# M044X.net
KiCad netlist of a schematic drawn in EAGLE
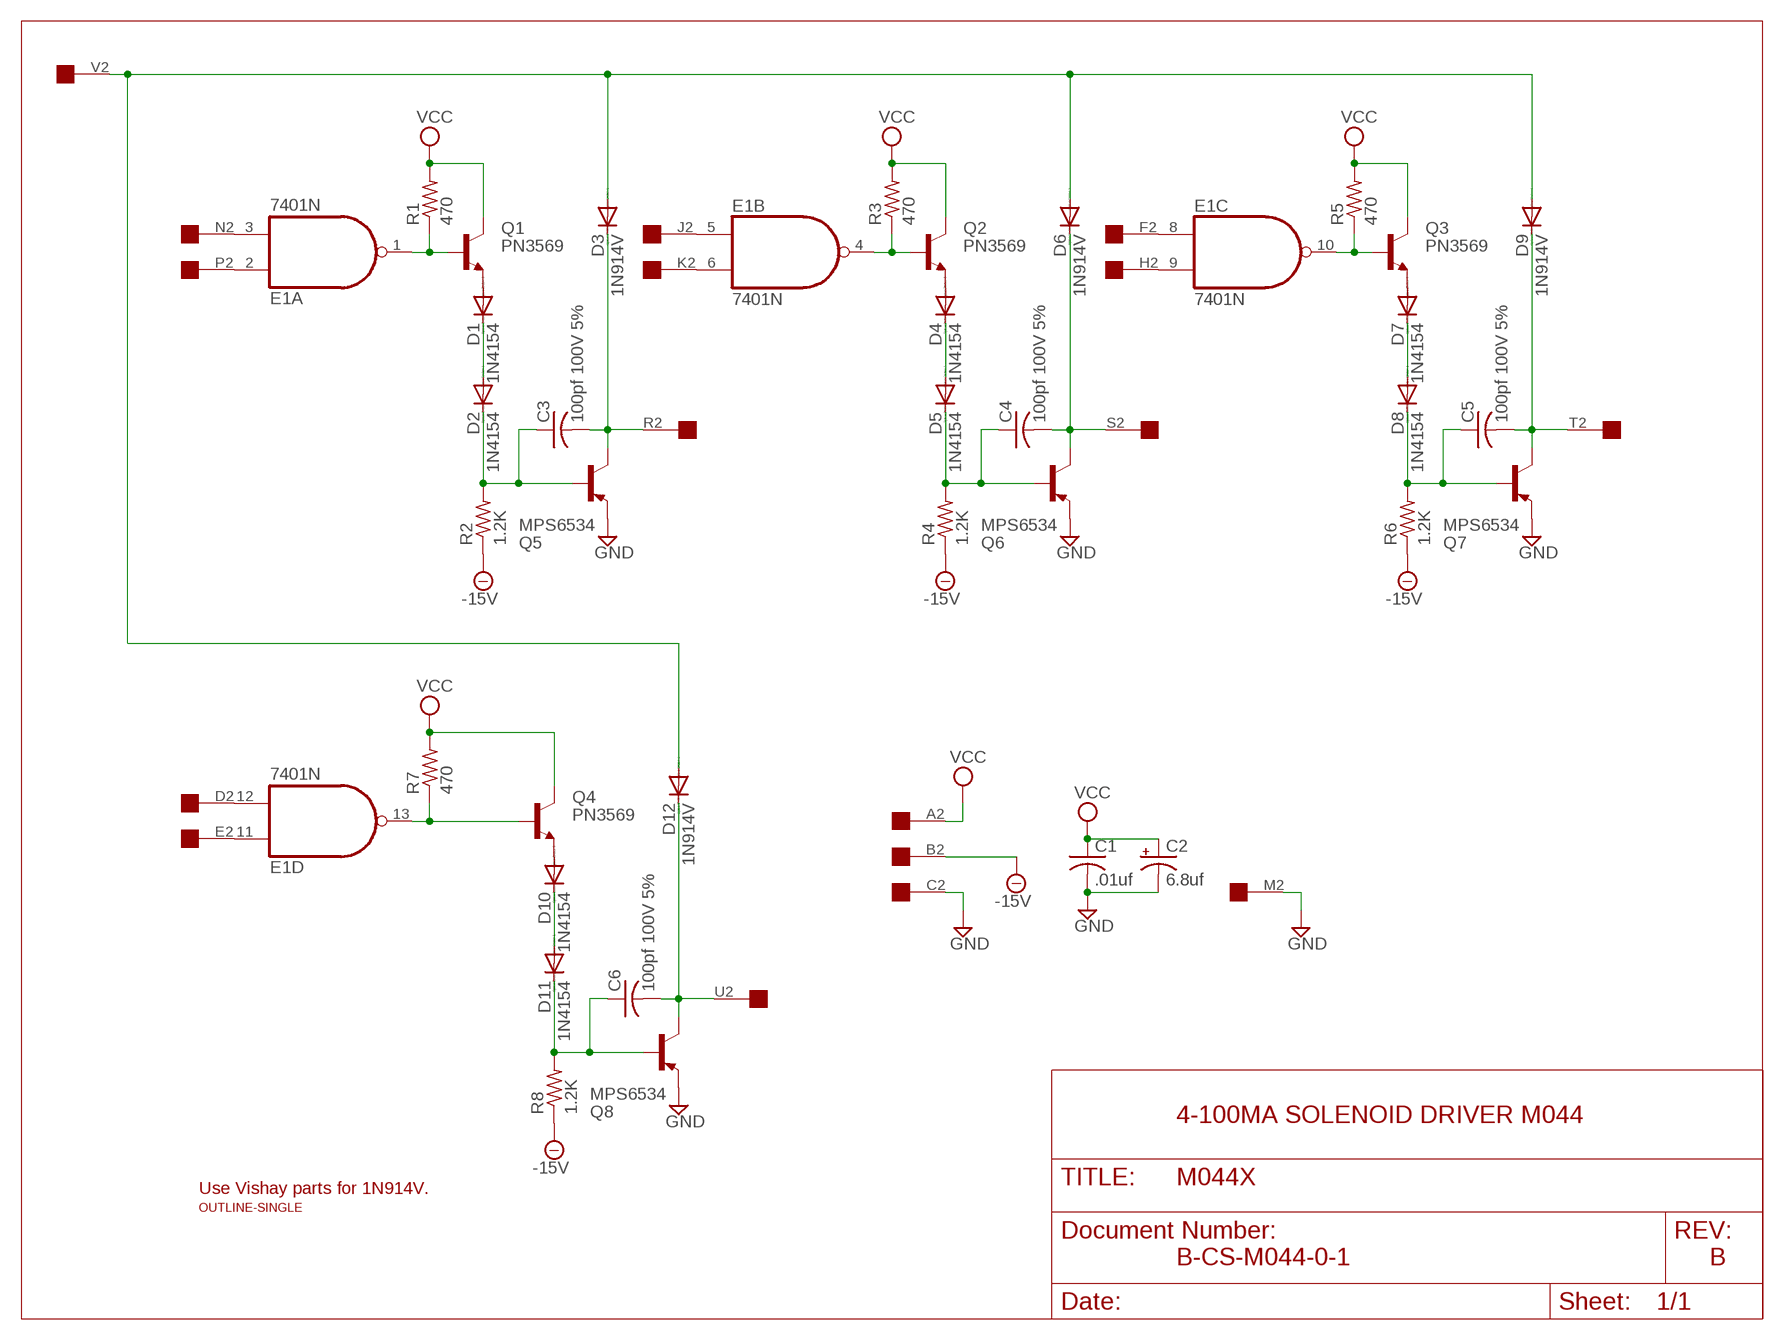
[diagram p0: schematic, sheet 1]

(export (version "E")
  (design (tool "Eeschema 10.0.6"))
  (components
    (comp (ref "C1")
      (value ".01uf")
      (footprint "eagle-import:C050-025X075")
      (libsource (lib "eagle-import") (part "C-US050-025X075"))
    )
    (comp (ref "C2")
      (value "6.8uf")
      (footprint "eagle-import:E15-5")
      (libsource (lib "eagle-import") (part "CPOL-USE15-5AXIAL"))
    )
    (comp (ref "C3")
      (value "100pf 100V 5%")
      (footprint "eagle-import:C050-025X075")
      (libsource (lib "eagle-import") (part "C-US050-025X075"))
    )
    (comp (ref "C4")
      (value "100pf 100V 5%")
      (footprint "eagle-import:C050-025X075")
      (libsource (lib "eagle-import") (part "C-US050-025X075"))
    )
    (comp (ref "C5")
      (value "100pf 100V 5%")
      (footprint "eagle-import:C050-025X075")
      (libsource (lib "eagle-import") (part "C-US050-025X075"))
    )
    (comp (ref "C6")
      (value "100pf 100V 5%")
      (footprint "eagle-import:C050-025X075")
      (libsource (lib "eagle-import") (part "C-US050-025X075"))
    )
    (comp (ref "D1")
      (value "1N4154")
      (footprint "eagle-import:DO35-10")
      (libsource (lib "eagle-import") (part "1N4148DO35-10"))
    )
    (comp (ref "D2")
      (value "1N4154")
      (footprint "eagle-import:DO35-10")
      (libsource (lib "eagle-import") (part "1N4148DO35-10"))
    )
    (comp (ref "D3")
      (value "1N914V")
      (footprint "eagle-import:DO35-10")
      (libsource (lib "eagle-import") (part "1N4148DO35-10"))
    )
    (comp (ref "D4")
      (value "1N4154")
      (footprint "eagle-import:DO35-10")
      (libsource (lib "eagle-import") (part "1N4148DO35-10"))
    )
    (comp (ref "D5")
      (value "1N4154")
      (footprint "eagle-import:DO35-10")
      (libsource (lib "eagle-import") (part "1N4148DO35-10"))
    )
    (comp (ref "D6")
      (value "1N914V")
      (footprint "eagle-import:DO35-10")
      (libsource (lib "eagle-import") (part "1N4148DO35-10"))
    )
    (comp (ref "D7")
      (value "1N4154")
      (footprint "eagle-import:DO35-10")
      (libsource (lib "eagle-import") (part "1N4148DO35-10"))
    )
    (comp (ref "D8")
      (value "1N4154")
      (footprint "eagle-import:DO35-10")
      (libsource (lib "eagle-import") (part "1N4148DO35-10"))
    )
    (comp (ref "D9")
      (value "1N914V")
      (footprint "eagle-import:DO35-10")
      (libsource (lib "eagle-import") (part "1N4148DO35-10"))
    )
    (comp (ref "D10")
      (value "1N4154")
      (footprint "eagle-import:DO35-10")
      (libsource (lib "eagle-import") (part "1N4148DO35-10"))
    )
    (comp (ref "D11")
      (value "1N4154")
      (footprint "eagle-import:DO35-10")
      (libsource (lib "eagle-import") (part "1N4148DO35-10"))
    )
    (comp (ref "D12")
      (value "1N914V")
      (footprint "eagle-import:DO35-10")
      (libsource (lib "eagle-import") (part "1N4148DO35-10"))
    )
    (comp (ref "E1")
      (value "7401N")
      (footprint "eagle-import:DIL14")
      (libsource (lib "eagle-import") (part "7401NLS"))
    )
    (comp (ref "Q1")
      (value "PN3569")
      (footprint "eagle-import:TO39")
      (libsource (lib "eagle-import") (part "2N3019"))
    )
    (comp (ref "Q2")
      (value "PN3569")
      (footprint "eagle-import:TO39")
      (libsource (lib "eagle-import") (part "2N3019"))
    )
    (comp (ref "Q3")
      (value "PN3569")
      (footprint "eagle-import:TO39")
      (libsource (lib "eagle-import") (part "2N3019"))
    )
    (comp (ref "Q4")
      (value "PN3569")
      (footprint "eagle-import:TO39")
      (libsource (lib "eagle-import") (part "2N3019"))
    )
    (comp (ref "Q5")
      (value "MPS6534")
      (footprint "eagle-import:TO39")
      (libsource (lib "eagle-import") (part "-PNP-TO39-EBC2N2904"))
    )
    (comp (ref "Q6")
      (value "MPS6534")
      (footprint "eagle-import:TO39")
      (libsource (lib "eagle-import") (part "-PNP-TO39-EBC2N2904"))
    )
    (comp (ref "Q7")
      (value "MPS6534")
      (footprint "eagle-import:TO39")
      (libsource (lib "eagle-import") (part "-PNP-TO39-EBC2N2904"))
    )
    (comp (ref "Q8")
      (value "MPS6534")
      (footprint "eagle-import:TO39")
      (libsource (lib "eagle-import") (part "-PNP-TO39-EBC2N2904"))
    )
    (comp (ref "R1")
      (value "470")
      (footprint "eagle-import:0207_10")
      (libsource (lib "eagle-import") (part "R-US_0207/10"))
    )
    (comp (ref "R2")
      (value "1.2K")
      (footprint "eagle-import:0207_10")
      (libsource (lib "eagle-import") (part "R-US_0207/10"))
    )
    (comp (ref "R3")
      (value "470")
      (footprint "eagle-import:0207_10")
      (libsource (lib "eagle-import") (part "R-US_0207/10"))
    )
    (comp (ref "R4")
      (value "1.2K")
      (footprint "eagle-import:0207_10")
      (libsource (lib "eagle-import") (part "R-US_0207/10"))
    )
    (comp (ref "R5")
      (value "470")
      (footprint "eagle-import:0207_10")
      (libsource (lib "eagle-import") (part "R-US_0207/10"))
    )
    (comp (ref "R6")
      (value "1.2K")
      (footprint "eagle-import:0207_10")
      (libsource (lib "eagle-import") (part "R-US_0207/10"))
    )
    (comp (ref "R7")
      (value "470")
      (footprint "eagle-import:0207_10")
      (libsource (lib "eagle-import") (part "R-US_0207/10"))
    )
    (comp (ref "R8")
      (value "1.2K")
      (footprint "eagle-import:0207_10")
      (libsource (lib "eagle-import") (part "R-US_0207/10"))
    )
    (comp (ref "U$1")
      (value "OUTLINE-SINGLE")
      (footprint "eagle-import:SINGLE")
      (libsource (lib "eagle-import") (part "OUTLINE-SINGLE"))
    )
    (comp (ref "U$2")
      (value "EDGE-1")
      (footprint "eagle-import:EDGE-CON1")
      (libsource (lib "eagle-import") (part "EDGE-1"))
    )
  )
  (nets
    (net (code "1") (name "-15V") (class "Default")
      (node (ref "R2") (pin "1") (pinfunction "1_1") (pintype "passive"))
      (node (ref "R4") (pin "1") (pinfunction "1_1") (pintype "passive"))
      (node (ref "R6") (pin "1") (pinfunction "1_1") (pintype "passive"))
      (node (ref "R8") (pin "1") (pinfunction "1_1") (pintype "passive"))
      (node (ref "U$2") (pin "B2") (pinfunction "1_B2") (pintype "bidirectional"))
    )
    (net (code "2") (name "GND") (class "Default")
      (node (ref "C1") (pin "2") (pinfunction "2_2") (pintype "passive"))
      (node (ref "C2") (pin "-") (pinfunction "-_-") (pintype "passive"))
      (node (ref "Q5") (pin "1") (pinfunction "E_1") (pintype "passive"))
      (node (ref "Q6") (pin "1") (pinfunction "E_1") (pintype "passive"))
      (node (ref "Q7") (pin "1") (pinfunction "E_1") (pintype "passive"))
      (node (ref "Q8") (pin "1") (pinfunction "E_1") (pintype "passive"))
      (node (ref "U$2") (pin "C2") (pinfunction "1_C2") (pintype "bidirectional"))
      (node (ref "U$2") (pin "M2") (pinfunction "1_M2") (pintype "bidirectional"))
    )
    (net (code "3") (name "Net-(D1-PadC)") (class "Default")
      (node (ref "D1") (pin "C") (pinfunction "C_C") (pintype "passive"))
      (node (ref "D2") (pin "A") (pinfunction "A_A") (pintype "passive"))
    )
    (net (code "4") (name "Net-(D4-PadC)") (class "Default")
      (node (ref "D4") (pin "C") (pinfunction "C_C") (pintype "passive"))
      (node (ref "D5") (pin "A") (pinfunction "A_A") (pintype "passive"))
    )
    (net (code "5") (name "Net-(D7-PadC)") (class "Default")
      (node (ref "D7") (pin "C") (pinfunction "C_C") (pintype "passive"))
      (node (ref "D8") (pin "A") (pinfunction "A_A") (pintype "passive"))
    )
    (net (code "6") (name "Net-(D10-PadC)") (class "Default")
      (node (ref "D10") (pin "C") (pinfunction "C_C") (pintype "passive"))
      (node (ref "D11") (pin "A") (pinfunction "A_A") (pintype "passive"))
    )
    (net (code "7") (name "Net-(E1A-I0)") (class "Default")
      (node (ref "E1") (pin "2") (pinfunction "I0_2") (pintype "input"))
      (node (ref "U$2") (pin "P2") (pinfunction "1_P2") (pintype "bidirectional"))
    )
    (net (code "8") (name "Net-(E1A-I1)") (class "Default")
      (node (ref "E1") (pin "3") (pinfunction "I1_3") (pintype "input"))
      (node (ref "U$2") (pin "N2") (pinfunction "1_N2") (pintype "bidirectional"))
    )
    (net (code "9") (name "Net-(E1A-O)") (class "Default")
      (node (ref "E1") (pin "1") (pinfunction "O_1") (pintype "open_collector"))
      (node (ref "Q1") (pin "2") (pinfunction "B_2") (pintype "passive"))
      (node (ref "R1") (pin "1") (pinfunction "1_1") (pintype "passive"))
    )
    (net (code "10") (name "Net-(E1B-I0)") (class "Default")
      (node (ref "E1") (pin "5") (pinfunction "I0_5") (pintype "input"))
      (node (ref "U$2") (pin "J2") (pinfunction "1_J2") (pintype "bidirectional"))
    )
    (net (code "11") (name "Net-(E1B-I1)") (class "Default")
      (node (ref "E1") (pin "6") (pinfunction "I1_6") (pintype "input"))
      (node (ref "U$2") (pin "K2") (pinfunction "1_K2") (pintype "bidirectional"))
    )
    (net (code "12") (name "Net-(E1B-O)") (class "Default")
      (node (ref "E1") (pin "4") (pinfunction "O_4") (pintype "open_collector"))
      (node (ref "Q2") (pin "2") (pinfunction "B_2") (pintype "passive"))
      (node (ref "R3") (pin "1") (pinfunction "1_1") (pintype "passive"))
    )
    (net (code "13") (name "Net-(E1C-I0)") (class "Default")
      (node (ref "E1") (pin "8") (pinfunction "I0_8") (pintype "input"))
      (node (ref "U$2") (pin "F2") (pinfunction "1_F2") (pintype "bidirectional"))
    )
    (net (code "14") (name "Net-(E1C-I1)") (class "Default")
      (node (ref "E1") (pin "9") (pinfunction "I1_9") (pintype "input"))
      (node (ref "U$2") (pin "H2") (pinfunction "1_H2") (pintype "bidirectional"))
    )
    (net (code "15") (name "Net-(E1C-O)") (class "Default")
      (node (ref "E1") (pin "10") (pinfunction "O_10") (pintype "open_collector"))
      (node (ref "Q3") (pin "2") (pinfunction "B_2") (pintype "passive"))
      (node (ref "R5") (pin "1") (pinfunction "1_1") (pintype "passive"))
    )
    (net (code "16") (name "Net-(E1D-I0)") (class "Default")
      (node (ref "E1") (pin "11") (pinfunction "I0_11") (pintype "input"))
      (node (ref "U$2") (pin "E2") (pinfunction "1_E2") (pintype "bidirectional"))
    )
    (net (code "17") (name "Net-(E1D-I1)") (class "Default")
      (node (ref "E1") (pin "12") (pinfunction "I1_12") (pintype "input"))
      (node (ref "U$2") (pin "D2") (pinfunction "1_D2") (pintype "bidirectional"))
    )
    (net (code "18") (name "Net-(E1D-O)") (class "Default")
      (node (ref "E1") (pin "13") (pinfunction "O_13") (pintype "open_collector"))
      (node (ref "Q4") (pin "2") (pinfunction "B_2") (pintype "passive"))
      (node (ref "R7") (pin "1") (pinfunction "1_1") (pintype "passive"))
    )
    (net (code "19") (name "Net-(Q1-E)") (class "Default")
      (node (ref "D1") (pin "A") (pinfunction "A_A") (pintype "passive"))
      (node (ref "Q1") (pin "1") (pinfunction "E_1") (pintype "passive"))
    )
    (net (code "20") (name "Net-(Q2-E)") (class "Default")
      (node (ref "D4") (pin "A") (pinfunction "A_A") (pintype "passive"))
      (node (ref "Q2") (pin "1") (pinfunction "E_1") (pintype "passive"))
    )
    (net (code "21") (name "Net-(Q3-E)") (class "Default")
      (node (ref "D7") (pin "A") (pinfunction "A_A") (pintype "passive"))
      (node (ref "Q3") (pin "1") (pinfunction "E_1") (pintype "passive"))
    )
    (net (code "22") (name "Net-(Q4-E)") (class "Default")
      (node (ref "D10") (pin "A") (pinfunction "A_A") (pintype "passive"))
      (node (ref "Q4") (pin "1") (pinfunction "E_1") (pintype "passive"))
    )
    (net (code "23") (name "Net-(Q5-B)") (class "Default")
      (node (ref "C3") (pin "1") (pinfunction "1_1") (pintype "passive"))
      (node (ref "D2") (pin "C") (pinfunction "C_C") (pintype "passive"))
      (node (ref "Q5") (pin "2") (pinfunction "B_2") (pintype "passive"))
      (node (ref "R2") (pin "2") (pinfunction "2_2") (pintype "passive"))
    )
    (net (code "24") (name "Net-(Q5-C)") (class "Default")
      (node (ref "C3") (pin "2") (pinfunction "2_2") (pintype "passive"))
      (node (ref "D3") (pin "C") (pinfunction "C_C") (pintype "passive"))
      (node (ref "Q5") (pin "3") (pinfunction "C_3") (pintype "passive"))
      (node (ref "U$2") (pin "R2") (pinfunction "1_R2") (pintype "bidirectional"))
    )
    (net (code "25") (name "Net-(Q6-B)") (class "Default")
      (node (ref "C4") (pin "1") (pinfunction "1_1") (pintype "passive"))
      (node (ref "D5") (pin "C") (pinfunction "C_C") (pintype "passive"))
      (node (ref "Q6") (pin "2") (pinfunction "B_2") (pintype "passive"))
      (node (ref "R4") (pin "2") (pinfunction "2_2") (pintype "passive"))
    )
    (net (code "26") (name "Net-(Q6-C)") (class "Default")
      (node (ref "C4") (pin "2") (pinfunction "2_2") (pintype "passive"))
      (node (ref "D6") (pin "C") (pinfunction "C_C") (pintype "passive"))
      (node (ref "Q6") (pin "3") (pinfunction "C_3") (pintype "passive"))
      (node (ref "U$2") (pin "S2") (pinfunction "1_S2") (pintype "bidirectional"))
    )
    (net (code "27") (name "Net-(Q7-B)") (class "Default")
      (node (ref "C5") (pin "1") (pinfunction "1_1") (pintype "passive"))
      (node (ref "D8") (pin "C") (pinfunction "C_C") (pintype "passive"))
      (node (ref "Q7") (pin "2") (pinfunction "B_2") (pintype "passive"))
      (node (ref "R6") (pin "2") (pinfunction "2_2") (pintype "passive"))
    )
    (net (code "28") (name "Net-(Q7-C)") (class "Default")
      (node (ref "C5") (pin "2") (pinfunction "2_2") (pintype "passive"))
      (node (ref "D9") (pin "C") (pinfunction "C_C") (pintype "passive"))
      (node (ref "Q7") (pin "3") (pinfunction "C_3") (pintype "passive"))
      (node (ref "U$2") (pin "T2") (pinfunction "1_T2") (pintype "bidirectional"))
    )
    (net (code "29") (name "Net-(Q8-B)") (class "Default")
      (node (ref "C6") (pin "1") (pinfunction "1_1") (pintype "passive"))
      (node (ref "D11") (pin "C") (pinfunction "C_C") (pintype "passive"))
      (node (ref "Q8") (pin "2") (pinfunction "B_2") (pintype "passive"))
      (node (ref "R8") (pin "2") (pinfunction "2_2") (pintype "passive"))
    )
    (net (code "30") (name "Net-(Q8-C)") (class "Default")
      (node (ref "C6") (pin "2") (pinfunction "2_2") (pintype "passive"))
      (node (ref "D12") (pin "C") (pinfunction "C_C") (pintype "passive"))
      (node (ref "Q8") (pin "3") (pinfunction "C_3") (pintype "passive"))
      (node (ref "U$2") (pin "U2") (pinfunction "1_U2") (pintype "bidirectional"))
    )
    (net (code "31") (name "Net-(U$2R-1)") (class "Default")
      (node (ref "D12") (pin "A") (pinfunction "A_A") (pintype "passive"))
      (node (ref "D3") (pin "A") (pinfunction "A_A") (pintype "passive"))
      (node (ref "D6") (pin "A") (pinfunction "A_A") (pintype "passive"))
      (node (ref "D9") (pin "A") (pinfunction "A_A") (pintype "passive"))
      (node (ref "U$2") (pin "V2") (pinfunction "1_V2") (pintype "bidirectional"))
    )
    (net (code "32") (name "VCC") (class "Default")
      (node (ref "C1") (pin "1") (pinfunction "1_1") (pintype "passive"))
      (node (ref "C2") (pin "+") (pinfunction "+_+") (pintype "passive"))
      (node (ref "Q1") (pin "3") (pinfunction "C_3") (pintype "passive"))
      (node (ref "Q2") (pin "3") (pinfunction "C_3") (pintype "passive"))
      (node (ref "Q3") (pin "3") (pinfunction "C_3") (pintype "passive"))
      (node (ref "Q4") (pin "3") (pinfunction "C_3") (pintype "passive"))
      (node (ref "R1") (pin "2") (pinfunction "2_2") (pintype "passive"))
      (node (ref "R3") (pin "2") (pinfunction "2_2") (pintype "passive"))
      (node (ref "R5") (pin "2") (pinfunction "2_2") (pintype "passive"))
      (node (ref "R7") (pin "2") (pinfunction "2_2") (pintype "passive"))
      (node (ref "U$2") (pin "A2") (pinfunction "1_A2") (pintype "bidirectional"))
    )
  )
)
